# trackuino-simple.net
KiCad netlist of a schematic drawn in EAGLE
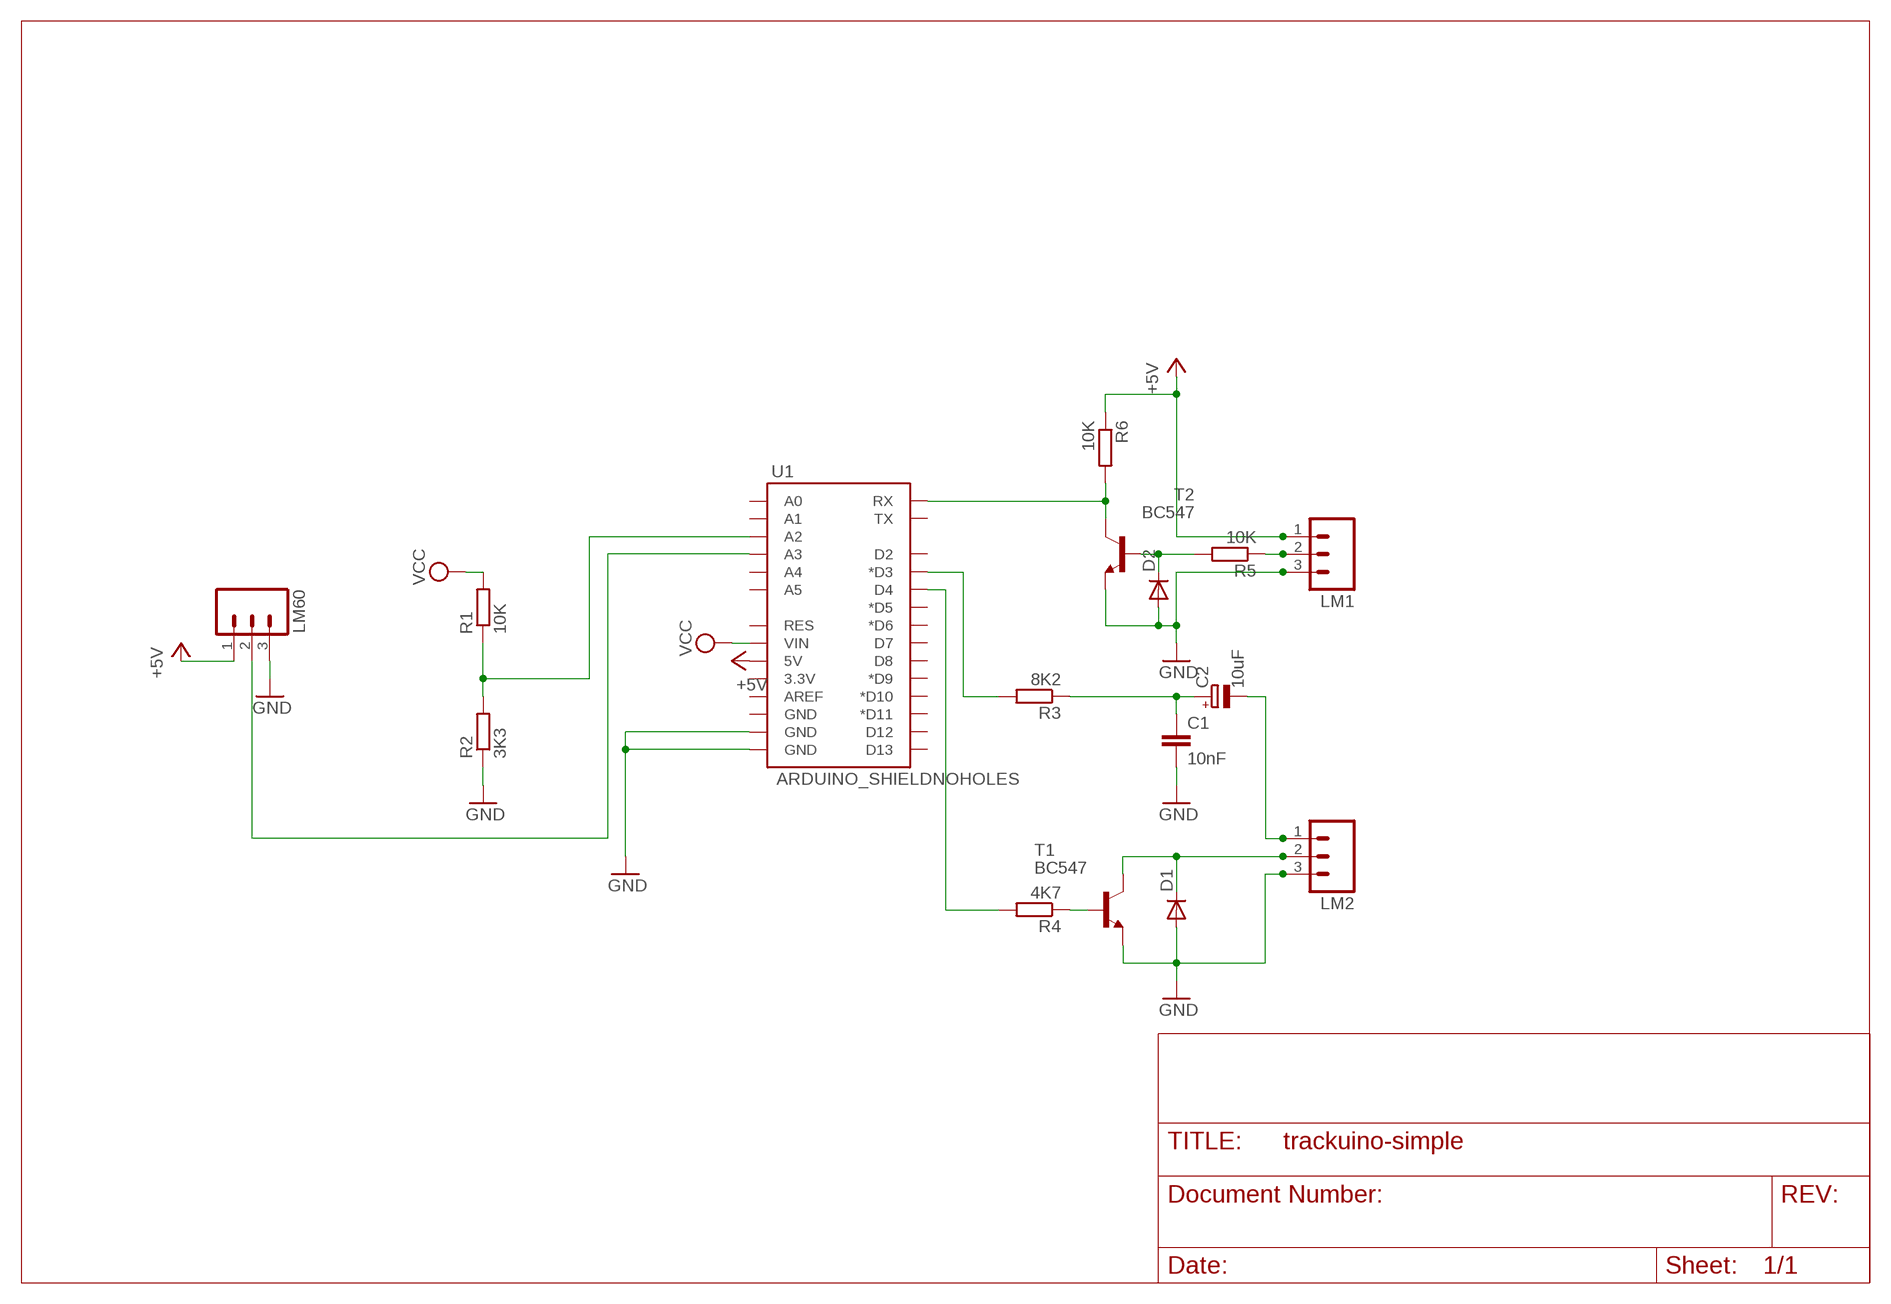
[diagram p0: schematic, sheet 1]

(export (version "E")
  (design (tool "Eeschema 10.0.6"))
  (components
    (comp (ref "C1")
      (value "10nF")
      (footprint "eagle-import:C050-025X075")
      (libsource (lib "eagle-import") (part "C-EU050-025X075"))
    )
    (comp (ref "C2")
      (value "10uF")
      (footprint "eagle-import:E2,5-6")
      (libsource (lib "eagle-import") (part "CPOL-EUE2.5-6"))
    )
    (comp (ref "D1")
      (value "DIODE-DO41-10")
      (footprint "eagle-import:DO41-10")
      (libsource (lib "eagle-import") (part "DIODE-DO41-10"))
    )
    (comp (ref "D2")
      (value "DIODE-DO41-10")
      (footprint "eagle-import:DO41-10")
      (libsource (lib "eagle-import") (part "DIODE-DO41-10"))
    )
    (comp (ref "LM1")
      (value "M03PTH")
      (footprint "eagle-import:1X03")
      (libsource (lib "eagle-import") (part "M03PTH"))
    )
    (comp (ref "LM2")
      (value "M03PTH")
      (footprint "eagle-import:1X03")
      (libsource (lib "eagle-import") (part "M03PTH"))
    )
    (comp (ref "LM60")
      (value "M03PTH")
      (footprint "eagle-import:1X03")
      (libsource (lib "eagle-import") (part "M03PTH"))
    )
    (comp (ref "R1")
      (value "10K")
      (footprint "eagle-import:0207_10")
      (libsource (lib "eagle-import") (part "R-EU_0207/10"))
    )
    (comp (ref "R2")
      (value "3K3")
      (footprint "eagle-import:0207_10")
      (libsource (lib "eagle-import") (part "R-EU_0207/10"))
    )
    (comp (ref "R3")
      (value "8K2")
      (footprint "eagle-import:0207_10")
      (libsource (lib "eagle-import") (part "R-EU_0207/10"))
    )
    (comp (ref "R4")
      (value "4K7")
      (footprint "eagle-import:0207_10")
      (libsource (lib "eagle-import") (part "R-EU_0207/10"))
    )
    (comp (ref "R5")
      (value "10K")
      (footprint "eagle-import:0207_10")
      (libsource (lib "eagle-import") (part "resistor_R-EU_0207/10"))
    )
    (comp (ref "R6")
      (value "10K")
      (footprint "eagle-import:0207_10")
      (libsource (lib "eagle-import") (part "resistor_R-EU_0207/10"))
    )
    (comp (ref "T1")
      (value "BC547")
      (footprint "eagle-import:TO92")
      (libsource (lib "eagle-import") (part "BC547"))
    )
    (comp (ref "T2")
      (value "BC547")
      (footprint "eagle-import:TO92")
      (libsource (lib "eagle-import") (part "BC547"))
    )
    (comp (ref "U1")
      (value "ARDUINO_SHIELDNOHOLES")
      (footprint "eagle-import:DUEMILANOVE_SHIELD_NOHOLES")
      (libsource (lib "eagle-import") (part "ARDUINO_SHIELDNOHOLES"))
    )
  )
  (nets
    (net (code "1") (name "+5V") (class "Default")
      (node (ref "LM1") (pin "1") (pinfunction "1_1") (pintype "passive"))
      (node (ref "LM60") (pin "1") (pinfunction "1_1") (pintype "passive"))
      (node (ref "R6") (pin "1") (pinfunction "1_1") (pintype "passive"))
      (node (ref "U1") (pin "5V") (pinfunction "5V_5V") (pintype "bidirectional"))
    )
    (net (code "2") (name "GND") (class "Default")
      (node (ref "C1") (pin "2") (pinfunction "2_2") (pintype "passive"))
      (node (ref "D1") (pin "A") (pinfunction "A_A") (pintype "passive"))
      (node (ref "D2") (pin "A") (pinfunction "A_A") (pintype "passive"))
      (node (ref "LM1") (pin "3") (pinfunction "3_3") (pintype "passive"))
      (node (ref "LM2") (pin "3") (pinfunction "3_3") (pintype "passive"))
      (node (ref "LM60") (pin "3") (pinfunction "3_3") (pintype "passive"))
      (node (ref "R2") (pin "1") (pinfunction "1_1") (pintype "passive"))
      (node (ref "T1") (pin "1") (pinfunction "E_1") (pintype "passive"))
      (node (ref "T2") (pin "1") (pinfunction "E_1") (pintype "passive"))
      (node (ref "U1") (pin "GND@0") (pinfunction "GND_GND@0") (pintype "bidirectional"))
      (node (ref "U1") (pin "GND@1") (pinfunction "GND_GND@1") (pintype "bidirectional"))
    )
    (net (code "3") (name "Net-(C1-Pad1)") (class "Default")
      (node (ref "C1") (pin "1") (pinfunction "1_1") (pintype "passive"))
      (node (ref "C2") (pin "+") (pinfunction "+_+") (pintype "passive"))
      (node (ref "R3") (pin "1") (pinfunction "1_1") (pintype "passive"))
    )
    (net (code "4") (name "Net-(C2-Pad-)") (class "Default")
      (node (ref "C2") (pin "-") (pinfunction "-_-") (pintype "passive"))
      (node (ref "LM2") (pin "1") (pinfunction "1_1") (pintype "passive"))
    )
    (net (code "5") (name "Net-(LM1-Pad2)") (class "Default")
      (node (ref "LM1") (pin "2") (pinfunction "2_2") (pintype "passive"))
      (node (ref "R5") (pin "1") (pinfunction "1_1") (pintype "passive"))
    )
    (net (code "6") (name "Net-(LM60-Pad2)") (class "Default")
      (node (ref "LM60") (pin "2") (pinfunction "2_2") (pintype "passive"))
      (node (ref "U1") (pin "A3") (pinfunction "A3_A3") (pintype "bidirectional"))
    )
    (net (code "7") (name "Net-(R1-Pad1)") (class "Default")
      (node (ref "R1") (pin "1") (pinfunction "1_1") (pintype "passive"))
      (node (ref "R2") (pin "2") (pinfunction "2_2") (pintype "passive"))
      (node (ref "U1") (pin "A2") (pinfunction "A2_A2") (pintype "bidirectional"))
    )
    (net (code "8") (name "Net-(R4-Pad2)") (class "Default")
      (node (ref "R4") (pin "2") (pinfunction "2_2") (pintype "passive"))
      (node (ref "U1") (pin "D4") (pinfunction "D4_D4") (pintype "bidirectional"))
    )
    (net (code "9") (name "Net-(T1-B)") (class "Default")
      (node (ref "R4") (pin "1") (pinfunction "1_1") (pintype "passive"))
      (node (ref "T1") (pin "2") (pinfunction "B_2") (pintype "passive"))
    )
    (net (code "10") (name "Net-(T1-C)") (class "Default")
      (node (ref "D1") (pin "C") (pinfunction "C_C") (pintype "passive"))
      (node (ref "LM2") (pin "2") (pinfunction "2_2") (pintype "passive"))
      (node (ref "T1") (pin "3") (pinfunction "C_3") (pintype "passive"))
    )
    (net (code "11") (name "Net-(T2-B)") (class "Default")
      (node (ref "D2") (pin "C") (pinfunction "C_C") (pintype "passive"))
      (node (ref "R5") (pin "2") (pinfunction "2_2") (pintype "passive"))
      (node (ref "T2") (pin "2") (pinfunction "B_2") (pintype "passive"))
    )
    (net (code "12") (name "Net-(T2-C)") (class "Default")
      (node (ref "R6") (pin "2") (pinfunction "2_2") (pintype "passive"))
      (node (ref "T2") (pin "3") (pinfunction "C_3") (pintype "passive"))
      (node (ref "U1") (pin "RX") (pinfunction "RX_RX") (pintype "bidirectional"))
    )
    (net (code "13") (name "Net-(U1-*D3)") (class "Default")
      (node (ref "R3") (pin "2") (pinfunction "2_2") (pintype "passive"))
      (node (ref "U1") (pin "D3") (pinfunction "*D3_D3") (pintype "bidirectional"))
    )
    (net (code "14") (name "VCC") (class "Default")
      (node (ref "R1") (pin "2") (pinfunction "2_2") (pintype "passive"))
      (node (ref "U1") (pin "VIN") (pinfunction "VIN_VIN") (pintype "bidirectional"))
    )
    (net (code "15") (name "unconnected-(U1-*D5-PadD5)") (class "Default")
      (node (ref "U1") (pin "D5") (pinfunction "*D5_D5") (pintype "bidirectional"))
    )
    (net (code "16") (name "unconnected-(U1-*D6-PadD6)") (class "Default")
      (node (ref "U1") (pin "D6") (pinfunction "*D6_D6") (pintype "bidirectional"))
    )
    (net (code "17") (name "unconnected-(U1-*D9-PadD9)") (class "Default")
      (node (ref "U1") (pin "D9") (pinfunction "*D9_D9") (pintype "bidirectional"))
    )
    (net (code "18") (name "unconnected-(U1-*D10-PadD10)") (class "Default")
      (node (ref "U1") (pin "D10") (pinfunction "*D10_D10") (pintype "bidirectional"))
    )
    (net (code "19") (name "unconnected-(U1-*D11-PadD11)") (class "Default")
      (node (ref "U1") (pin "D11") (pinfunction "*D11_D11") (pintype "bidirectional"))
    )
    (net (code "20") (name "unconnected-(U1-GND-PadGND@2)") (class "Default")
      (node (ref "U1") (pin "GND@2") (pinfunction "GND_GND@2") (pintype "bidirectional"))
    )
    (net (code "21") (name "unconnected-(U1-Pad3.3V)") (class "Default")
      (node (ref "U1") (pin "3.3V") (pinfunction "3.3V_3.3V") (pintype "bidirectional"))
    )
    (net (code "22") (name "unconnected-(U1-PadA0)") (class "Default")
      (node (ref "U1") (pin "A0") (pinfunction "A0_A0") (pintype "bidirectional"))
    )
    (net (code "23") (name "unconnected-(U1-PadA1)") (class "Default")
      (node (ref "U1") (pin "A1") (pinfunction "A1_A1") (pintype "bidirectional"))
    )
    (net (code "24") (name "unconnected-(U1-PadA4)") (class "Default")
      (node (ref "U1") (pin "A4") (pinfunction "A4_A4") (pintype "bidirectional"))
    )
    (net (code "25") (name "unconnected-(U1-PadA5)") (class "Default")
      (node (ref "U1") (pin "A5") (pinfunction "A5_A5") (pintype "bidirectional"))
    )
    (net (code "26") (name "unconnected-(U1-PadAREF)") (class "Default")
      (node (ref "U1") (pin "AREF") (pinfunction "AREF_AREF") (pintype "bidirectional"))
    )
    (net (code "27") (name "unconnected-(U1-PadD2)") (class "Default")
      (node (ref "U1") (pin "D2") (pinfunction "D2_D2") (pintype "bidirectional"))
    )
    (net (code "28") (name "unconnected-(U1-PadD7)") (class "Default")
      (node (ref "U1") (pin "D7") (pinfunction "D7_D7") (pintype "bidirectional"))
    )
    (net (code "29") (name "unconnected-(U1-PadD8)") (class "Default")
      (node (ref "U1") (pin "D8") (pinfunction "D8_D8") (pintype "bidirectional"))
    )
    (net (code "30") (name "unconnected-(U1-PadD12)") (class "Default")
      (node (ref "U1") (pin "D12") (pinfunction "D12_D12") (pintype "bidirectional"))
    )
    (net (code "31") (name "unconnected-(U1-PadD13)") (class "Default")
      (node (ref "U1") (pin "D13") (pinfunction "D13_D13") (pintype "bidirectional"))
    )
    (net (code "32") (name "unconnected-(U1-PadRES)") (class "Default")
      (node (ref "U1") (pin "RES") (pinfunction "RES_RES") (pintype "bidirectional"))
    )
    (net (code "33") (name "unconnected-(U1-PadTX)") (class "Default")
      (node (ref "U1") (pin "TX") (pinfunction "TX_TX") (pintype "bidirectional"))
    )
  )
)
